# LNA_DIV.net
KiCad netlist of a schematic drawn in Altium Designer
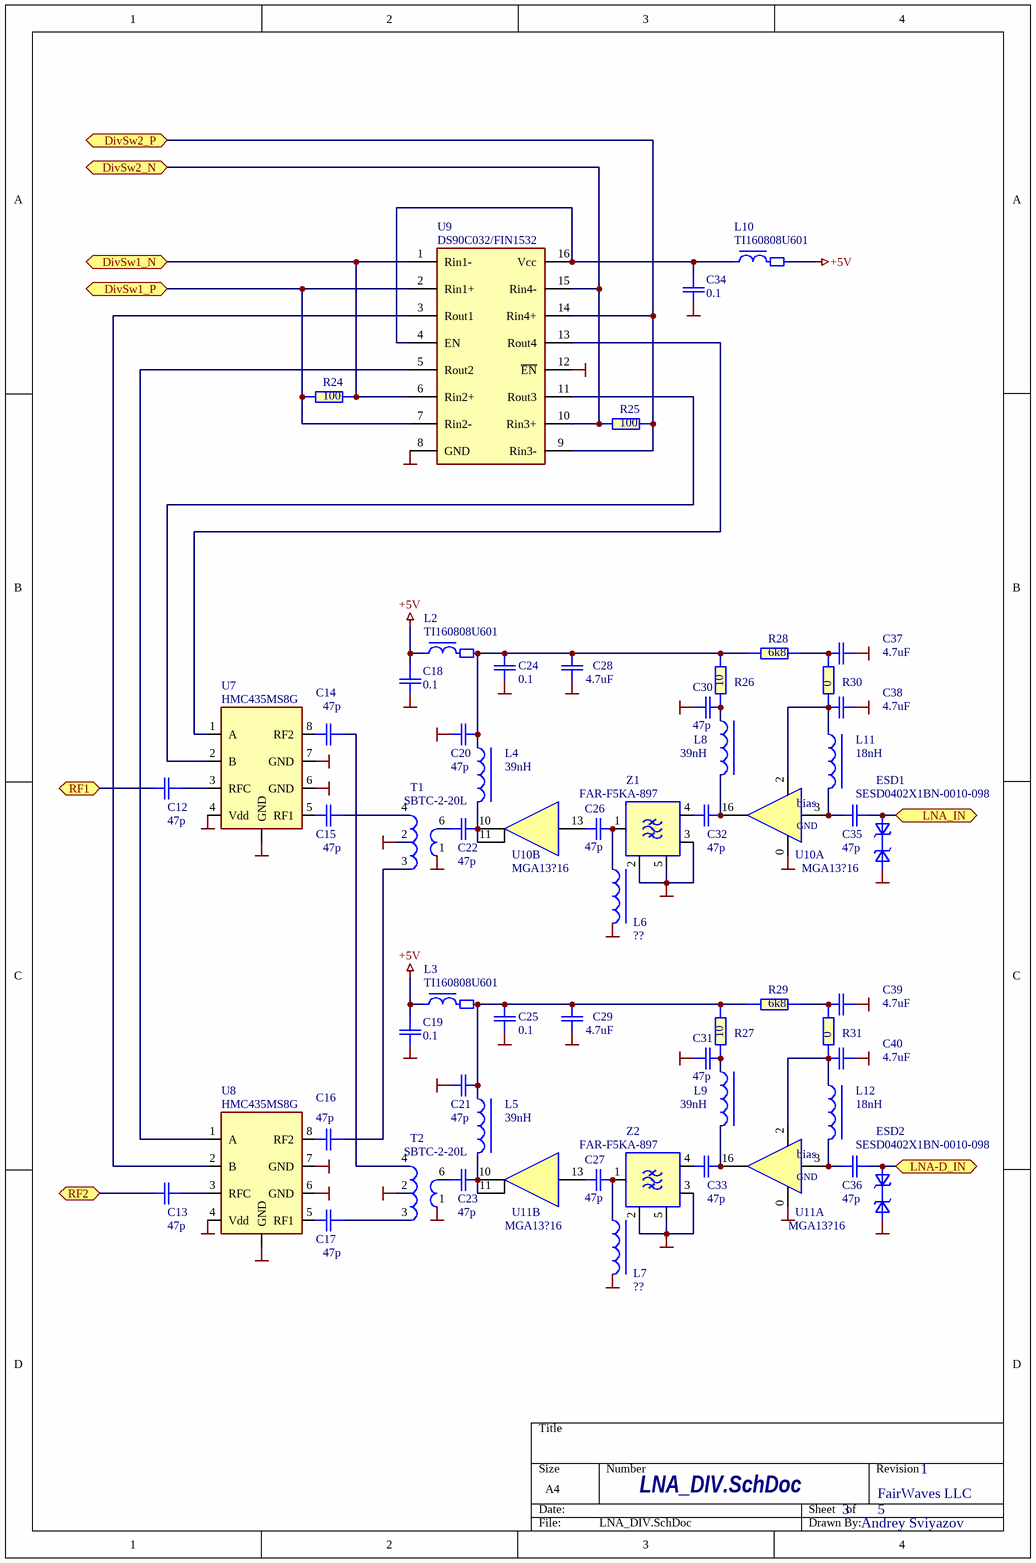
[diagram p0: LNA_DIV.SchDoc]

(export (version "E")
  (design (tool "Eeschema 10.0.6"))
  (components
    (comp (ref "C12")
      (value "47p")
      (footprint "C0603-PHILLIPS")
      (description "Capacitor")
      (fields (field (name "MANUFACTURER") "MURATA") (field (name "TOLERANCE") "20%"))
      (libsource (lib "altium-import") (part "root_1_C0603_"))
    )
    (comp (ref "C13")
      (value "47p")
      (footprint "C0603-PHILLIPS")
      (description "Capacitor")
      (fields (field (name "MANUFACTURER") "MURATA") (field (name "TOLERANCE") "20%"))
      (libsource (lib "altium-import") (part "root_1_C0603_"))
    )
    (comp (ref "C14")
      (value "47p")
      (footprint "C0603-PHILLIPS")
      (description "Capacitor")
      (fields (field (name "MANUFACTURER") "MURATA") (field (name "TOLERANCE") "20%"))
      (libsource (lib "altium-import") (part "root_1_C0603_"))
    )
    (comp (ref "C15")
      (value "47p")
      (footprint "C0603-PHILLIPS")
      (description "Capacitor")
      (fields (field (name "MANUFACTURER") "MURATA") (field (name "TOLERANCE") "20%"))
      (libsource (lib "altium-import") (part "root_1_C0603_"))
    )
    (comp (ref "C16")
      (value "47p")
      (footprint "C0603-PHILLIPS")
      (description "Capacitor")
      (fields (field (name "MANUFACTURER") "MURATA") (field (name "TOLERANCE") "20%"))
      (libsource (lib "altium-import") (part "root_1_C0603_"))
    )
    (comp (ref "C17")
      (value "47p")
      (footprint "C0603-PHILLIPS")
      (description "Capacitor")
      (fields (field (name "MANUFACTURER") "MURATA") (field (name "TOLERANCE") "20%"))
      (libsource (lib "altium-import") (part "root_1_C0603_"))
    )
    (comp (ref "C18")
      (value "0.1")
      (footprint "C0603-Phillips")
      (description "Capacitor")
      (fields (field (name "MANUFACTURER") "MURATA") (field (name "TOLERANCE") "20%"))
      (libsource (lib "Capacitors") (part "C0603"))
    )
    (comp (ref "C19")
      (value "0.1")
      (footprint "C0603-Phillips")
      (description "Capacitor")
      (fields (field (name "MANUFACTURER") "MURATA") (field (name "TOLERANCE") "20%"))
      (libsource (lib "Capacitors") (part "C0603"))
    )
    (comp (ref "C20")
      (value "47p")
      (footprint "C0603-PHILLIPS")
      (description "Capacitor")
      (fields (field (name "MANUFACTURER") "MURATA") (field (name "TOLERANCE") "20%"))
      (libsource (lib "altium-import") (part "root_1_C0603_"))
    )
    (comp (ref "C21")
      (value "47p")
      (footprint "C0603-PHILLIPS")
      (description "Capacitor")
      (fields (field (name "MANUFACTURER") "MURATA") (field (name "TOLERANCE") "20%"))
      (libsource (lib "altium-import") (part "root_1_C0603_"))
    )
    (comp (ref "C22")
      (value "47p")
      (footprint "C0603-PHILLIPS")
      (description "Capacitor")
      (fields (field (name "MANUFACTURER") "MURATA") (field (name "TOLERANCE") "20%"))
      (libsource (lib "altium-import") (part "root_1_C0603_"))
    )
    (comp (ref "C23")
      (value "47p")
      (footprint "C0603-PHILLIPS")
      (description "Capacitor")
      (fields (field (name "MANUFACTURER") "MURATA") (field (name "TOLERANCE") "20%"))
      (libsource (lib "altium-import") (part "root_1_C0603_"))
    )
    (comp (ref "C24")
      (value "0.1")
      (footprint "C0603-Phillips")
      (description "Capacitor")
      (fields (field (name "MANUFACTURER") "MURATA") (field (name "TOLERANCE") "20%"))
      (libsource (lib "Capacitors") (part "C0603"))
    )
    (comp (ref "C25")
      (value "0.1")
      (footprint "C0603-Phillips")
      (description "Capacitor")
      (fields (field (name "MANUFACTURER") "MURATA") (field (name "TOLERANCE") "20%"))
      (libsource (lib "Capacitors") (part "C0603"))
    )
    (comp (ref "C26")
      (value "47p")
      (footprint "C0603-PHILLIPS")
      (description "Capacitor")
      (fields (field (name "MANUFACTURER") "MURATA") (field (name "TOLERANCE") "20%"))
      (libsource (lib "altium-import") (part "root_1_C0603_"))
    )
    (comp (ref "C27")
      (value "47p")
      (footprint "C0603-PHILLIPS")
      (description "Capacitor")
      (fields (field (name "MANUFACTURER") "MURATA") (field (name "TOLERANCE") "20%"))
      (libsource (lib "altium-import") (part "root_1_C0603_"))
    )
    (comp (ref "C28")
      (value "4.7uF")
      (footprint "C0603-Phillips")
      (description "Capacitor")
      (fields (field (name "MANUFACTURER") "MURATA") (field (name "TOLERANCE") "20%"))
      (libsource (lib "Capacitors") (part "C0603"))
    )
    (comp (ref "C29")
      (value "4.7uF")
      (footprint "C0603-Phillips")
      (description "Capacitor")
      (fields (field (name "MANUFACTURER") "MURATA") (field (name "TOLERANCE") "20%"))
      (libsource (lib "Capacitors") (part "C0603"))
    )
    (comp (ref "C30")
      (value "47p")
      (footprint "C0603-PHILLIPS")
      (description "Capacitor")
      (fields (field (name "MANUFACTURER") "MURATA") (field (name "TOLERANCE") "20%"))
      (libsource (lib "altium-import") (part "root_3_C0603_"))
    )
    (comp (ref "C31")
      (value "47p")
      (footprint "C0603-PHILLIPS")
      (description "Capacitor")
      (fields (field (name "MANUFACTURER") "MURATA") (field (name "TOLERANCE") "20%"))
      (libsource (lib "altium-import") (part "root_3_C0603_"))
    )
    (comp (ref "C32")
      (value "47p")
      (footprint "C0603-PHILLIPS")
      (description "Capacitor")
      (fields (field (name "MANUFACTURER") "MURATA") (field (name "TOLERANCE") "20%"))
      (libsource (lib "altium-import") (part "root_1_C0603_"))
    )
    (comp (ref "C33")
      (value "47p")
      (footprint "C0603-PHILLIPS")
      (description "Capacitor")
      (fields (field (name "MANUFACTURER") "MURATA") (field (name "TOLERANCE") "20%"))
      (libsource (lib "altium-import") (part "root_1_C0603_"))
    )
    (comp (ref "C34")
      (value "0.1")
      (footprint "C0603-Phillips")
      (description "Capacitor")
      (fields (field (name "MANUFACTURER") "MURATA") (field (name "TOLERANCE") "20%"))
      (libsource (lib "Capacitors") (part "C0603"))
    )
    (comp (ref "C35")
      (value "47p")
      (footprint "C0603-PHILLIPS")
      (description "Capacitor")
      (fields (field (name "MANUFACTURER") "MURATA") (field (name "TOLERANCE") "20%"))
      (libsource (lib "altium-import") (part "root_1_C0603_"))
    )
    (comp (ref "C36")
      (value "47p")
      (footprint "C0603-PHILLIPS")
      (description "Capacitor")
      (fields (field (name "MANUFACTURER") "MURATA") (field (name "TOLERANCE") "20%"))
      (libsource (lib "altium-import") (part "root_1_C0603_"))
    )
    (comp (ref "C37")
      (value "4.7uF")
      (footprint "C0603-Phillips")
      (description "Capacitor")
      (fields (field (name "MANUFACTURER") "MURATA") (field (name "TOLERANCE") "20%"))
      (libsource (lib "Capacitors") (part "C0603"))
    )
    (comp (ref "C38")
      (value "4.7uF")
      (footprint "C0603-Phillips")
      (description "Capacitor")
      (fields (field (name "MANUFACTURER") "MURATA") (field (name "TOLERANCE") "20%"))
      (libsource (lib "Capacitors") (part "C0603"))
    )
    (comp (ref "C39")
      (value "4.7uF")
      (footprint "C0603-Phillips")
      (description "Capacitor")
      (fields (field (name "MANUFACTURER") "MURATA") (field (name "TOLERANCE") "20%"))
      (libsource (lib "Capacitors") (part "C0603"))
    )
    (comp (ref "C40")
      (value "4.7uF")
      (footprint "C0603-Phillips")
      (description "Capacitor")
      (fields (field (name "MANUFACTURER") "MURATA") (field (name "TOLERANCE") "20%"))
      (libsource (lib "Capacitors") (part "C0603"))
    )
    (comp (ref "ESD1")
      (value "SESD0402X1BN-0010-098")
      (footprint "R0402-Phillips")
      (description "ESD diod bi-directional")
      (fields (field (name "MANUFACTURER") "Tyco Electronics Corp"))
      (libsource (lib "*") (part "SESD0402X"))
    )
    (comp (ref "ESD2")
      (value "SESD0402X1BN-0010-098")
      (footprint "R0402-Phillips")
      (description "ESD diod bi-directional")
      (fields (field (name "MANUFACTURER") "Tyco Electronics Corp"))
      (libsource (lib "*") (part "SESD0402X"))
    )
    (comp (ref "L2")
      (value "TI160808U601")
      (footprint "Andy:Ti160808-Phillips")
      (description "Choke")
      (fields (field (name "MANUFACTURER") "MURATA"))
      (libsource (lib "altium-import") (part "root_0_TI160808_"))
    )
    (comp (ref "L3")
      (value "TI160808U601")
      (footprint "Andy:Ti160808-Phillips")
      (description "Choke")
      (fields (field (name "MANUFACTURER") "MURATA"))
      (libsource (lib "altium-import") (part "root_0_TI160808_"))
    )
    (comp (ref "L4")
      (value "39nH")
      (footprint "Andy:TF160808-Phillips")
      (description "Coil")
      (fields (field (name "MANUFACTURER") "SMD"))
      (libsource (lib "altium-import") (part "root_3_TF160808_"))
    )
    (comp (ref "L5")
      (value "39nH")
      (footprint "Andy:TF160808-Phillips")
      (description "Coil")
      (fields (field (name "MANUFACTURER") "SMD"))
      (libsource (lib "altium-import") (part "root_3_TF160808_"))
    )
    (comp (ref "L6")
      (value "??")
      (footprint "TF160808-Phillips")
      (description "Coil")
      (fields (field (name "MANUFACTURER") "SMD"))
      (libsource (lib "Inductance Transformers") (part "TF160808"))
    )
    (comp (ref "L7")
      (value "??")
      (footprint "TF160808-Phillips")
      (description "Coil")
      (fields (field (name "MANUFACTURER") "SMD"))
      (libsource (lib "Inductance Transformers") (part "TF160808"))
    )
    (comp (ref "L8")
      (value "39nH")
      (footprint "Andy:TF160808-Phillips")
      (description "Coil")
      (fields (field (name "MANUFACTURER") "SMD"))
      (libsource (lib "altium-import") (part "root_3_TF160808_"))
    )
    (comp (ref "L9")
      (value "39nH")
      (footprint "Andy:TF160808-Phillips")
      (description "Coil")
      (fields (field (name "MANUFACTURER") "SMD"))
      (libsource (lib "altium-import") (part "root_3_TF160808_"))
    )
    (comp (ref "L10")
      (value "TI160808U601")
      (footprint "Andy:Ti160808-Phillips")
      (description "Choke")
      (fields (field (name "MANUFACTURER") "MURATA"))
      (libsource (lib "altium-import") (part "root_0_TI160808_"))
    )
    (comp (ref "L11")
      (value "18nH")
      (footprint "Andy:TF160808-Phillips")
      (description "Coil")
      (fields (field (name "MANUFACTURER") "SMD"))
      (libsource (lib "altium-import") (part "root_3_TF160808_"))
    )
    (comp (ref "L12")
      (value "18nH")
      (footprint "Andy:TF160808-Phillips")
      (description "Coil")
      (fields (field (name "MANUFACTURER") "SMD"))
      (libsource (lib "altium-import") (part "root_3_TF160808_"))
    )
    (comp (ref "R24")
      (value "100")
      (footprint "R0603-PHILLIPS")
      (description "Resistor")
      (fields (field (name "MANUFACTURER") "YAGEO") (field (name "TOLERANCE") "5%"))
      (libsource (lib "altium-import") (part "root_1_R0603_"))
    )
    (comp (ref "R25")
      (value "100")
      (footprint "R0603-PHILLIPS")
      (description "Resistor")
      (fields (field (name "MANUFACTURER") "YAGEO") (field (name "TOLERANCE") "5%"))
      (libsource (lib "altium-import") (part "root_1_R0603_"))
    )
    (comp (ref "R26")
      (value "10")
      (footprint "R0603-PHILLIPS")
      (description "Resistor")
      (fields (field (name "MANUFACTURER") "YAGEO") (field (name "TOLERANCE") "5%"))
      (libsource (lib "altium-import") (part "root_2_R0603_"))
    )
    (comp (ref "R27")
      (value "10")
      (footprint "R0603-PHILLIPS")
      (description "Resistor")
      (fields (field (name "MANUFACTURER") "YAGEO") (field (name "TOLERANCE") "5%"))
      (libsource (lib "altium-import") (part "root_2_R0603_"))
    )
    (comp (ref "R28")
      (value "6k8")
      (footprint "R0603-PHILLIPS")
      (description "Resistor")
      (fields (field (name "MANUFACTURER") "YAGEO") (field (name "TOLERANCE") "5%"))
      (libsource (lib "altium-import") (part "root_1_R0603_"))
    )
    (comp (ref "R29")
      (value "6k8")
      (footprint "R0603-PHILLIPS")
      (description "Resistor")
      (fields (field (name "MANUFACTURER") "YAGEO") (field (name "TOLERANCE") "5%"))
      (libsource (lib "altium-import") (part "root_1_R0603_"))
    )
    (comp (ref "R30")
      (value "0")
      (footprint "R0603-PHILLIPS")
      (description "Resistor")
      (fields (field (name "MANUFACTURER") "YAGEO") (field (name "TOLERANCE") "5%"))
      (libsource (lib "altium-import") (part "root_2_R0603_"))
    )
    (comp (ref "R31")
      (value "0")
      (footprint "R0603-PHILLIPS")
      (description "Resistor")
      (fields (field (name "MANUFACTURER") "YAGEO") (field (name "TOLERANCE") "5%"))
      (libsource (lib "altium-import") (part "root_2_R0603_"))
    )
    (comp (ref "T1")
      (value "SBTC-2-20L")
      (footprint "AT1030")
      (description "Transformer")
      (fields (field (name "MANUFACTURER") "Mini-Cirquits"))
      (libsource (lib "altium-import") (part "root_0_mirrored_SBTC-2-10L_"))
    )
    (comp (ref "T2")
      (value "SBTC-2-20L")
      (footprint "AT1030")
      (description "Transformer")
      (fields (field (name "MANUFACTURER") "Mini-Cirquits"))
      (libsource (lib "altium-import") (part "root_0_mirrored_SBTC-2-10L_"))
    )
    (comp (ref "U7")
      (value "HMC435MS8G")
      (footprint "MS8G")
      (description "IC")
      (fields (field (name "MANUFACTURER") "Hittite"))
      (libsource (lib "Andy") (part "HMC435MS8G"))
    )
    (comp (ref "U8")
      (value "HMC435MS8G")
      (footprint "MS8G")
      (description "IC")
      (fields (field (name "MANUFACTURER") "Hittite"))
      (libsource (lib "Andy") (part "HMC435MS8G"))
    )
    (comp (ref "U9")
      (value "DS90C032/FIN1532")
      (footprint "SOIC16")
      (description "IC")
      (fields (field (name "MANUFACTURER") "National/Fairchild"))
      (libsource (lib "Andy") (part "DS90C032"))
    )
    (comp (ref "U10")
      (value "MGA13?16")
      (footprint "MGA13x16(GND NC Legs)")
      (description "IC")
      (fields (field (name "MANUFACTURER") "AVAGO"))
      (libsource (lib "Andy") (part "MGA13116"))
    )
    (comp (ref "U11")
      (value "MGA13?16")
      (footprint "MGA13x16(GND NC Legs)")
      (description "IC")
      (fields (field (name "MANUFACTURER") "AVAGO"))
      (libsource (lib "Andy") (part "MGA13116"))
    )
    (comp (ref "Z1")
      (value "FAR-F5KA-897")
      (footprint "SAW-1.4x1x0.5mm")
      (description "SAW Filter")
      (fields (field (name "MANUFACTURER") "Taiyo Yuden"))
      (libsource (lib "Andy") (part "SAW 1.4x1.0-5 SMD"))
    )
    (comp (ref "Z2")
      (value "FAR-F5KA-897")
      (footprint "SAW-1.4x1x0.5mm")
      (description "SAW Filter")
      (fields (field (name "MANUFACTURER") "Taiyo Yuden"))
      (libsource (lib "Andy") (part "SAW 1.4x1.0-5 SMD"))
    )
  )
  (nets
    (net (code "1") (name "+5V") (class "Default")
      (node (ref "C18") (pin "2") (pinfunction "2_2") (pintype "passive"))
      (node (ref "C19") (pin "2") (pinfunction "2_2") (pintype "passive"))
      (node (ref "L10") (pin "2") (pinfunction "2_2") (pintype "passive"))
      (node (ref "L2") (pin "1") (pinfunction "1_1") (pintype "passive"))
      (node (ref "L3") (pin "1") (pinfunction "1_1") (pintype "passive"))
    )
    (net (code "2") (name "/DivSw1_N") (class "Default")
      (node (ref "R24") (pin "2") (pinfunction "2_2") (pintype "passive"))
      (node (ref "U9") (pin "1") (pinfunction "Rin1-_1") (pintype "passive"))
      (node (ref "U9") (pin "6") (pinfunction "Rin2+_6") (pintype "power_in"))
    )
    (net (code "3") (name "/DivSw1_P") (class "Default")
      (node (ref "R24") (pin "1") (pinfunction "1_1") (pintype "passive"))
      (node (ref "U9") (pin "2") (pinfunction "Rin1+_2") (pintype "passive"))
      (node (ref "U9") (pin "7") (pinfunction "Rin2-_7") (pintype "passive"))
    )
    (net (code "4") (name "/DivSw2_N") (class "Default")
      (node (ref "R25") (pin "1") (pinfunction "1_1") (pintype "passive"))
      (node (ref "U9") (pin "10") (pinfunction "Rin3+_10") (pintype "passive"))
      (node (ref "U9") (pin "15") (pinfunction "Rin4-_15") (pintype "passive"))
    )
    (net (code "5") (name "/DivSw2_P") (class "Default")
      (node (ref "R25") (pin "2") (pinfunction "2_2") (pintype "passive"))
      (node (ref "U9") (pin "14") (pinfunction "Rin4+_14") (pintype "power_in"))
      (node (ref "U9") (pin "9") (pinfunction "Rin3-_9") (pintype "passive"))
    )
    (net (code "6") (name "/LNA-D_IN") (class "Default")
      (node (ref "C36") (pin "2") (pinfunction "2_2") (pintype "passive"))
      (node (ref "ESD2") (pin "2") (pinfunction "A2_2") (pintype "passive"))
    )
    (net (code "7") (name "/LNA_IN") (class "Default")
      (node (ref "C35") (pin "2") (pinfunction "2_2") (pintype "passive"))
      (node (ref "ESD1") (pin "2") (pinfunction "A2_2") (pintype "passive"))
    )
    (net (code "8") (name "/RF1") (class "Default")
      (node (ref "C12") (pin "1") (pinfunction "1_1") (pintype "passive"))
    )
    (net (code "9") (name "/RF2") (class "Default")
      (node (ref "C13") (pin "1") (pinfunction "1_1") (pintype "passive"))
    )
    (net (code "10") (name "GND") (class "Default")
      (node (ref "C18") (pin "1") (pinfunction "1_1") (pintype "passive"))
      (node (ref "C19") (pin "1") (pinfunction "1_1") (pintype "passive"))
      (node (ref "C20") (pin "1") (pinfunction "1_1") (pintype "passive"))
      (node (ref "C21") (pin "1") (pinfunction "1_1") (pintype "passive"))
      (node (ref "C24") (pin "1") (pinfunction "1_1") (pintype "passive"))
      (node (ref "C25") (pin "1") (pinfunction "1_1") (pintype "passive"))
      (node (ref "C28") (pin "1") (pinfunction "1_1") (pintype "passive"))
      (node (ref "C29") (pin "1") (pinfunction "1_1") (pintype "passive"))
      (node (ref "C30") (pin "2") (pinfunction "2_2") (pintype "passive"))
      (node (ref "C31") (pin "2") (pinfunction "2_2") (pintype "passive"))
      (node (ref "C34") (pin "1") (pinfunction "1_1") (pintype "passive"))
      (node (ref "C37") (pin "2") (pinfunction "2_2") (pintype "passive"))
      (node (ref "C38") (pin "2") (pinfunction "2_2") (pintype "passive"))
      (node (ref "C39") (pin "2") (pinfunction "2_2") (pintype "passive"))
      (node (ref "C40") (pin "2") (pinfunction "2_2") (pintype "passive"))
      (node (ref "ESD1") (pin "1") (pinfunction "A1_1") (pintype "passive"))
      (node (ref "ESD2") (pin "1") (pinfunction "A1_1") (pintype "passive"))
      (node (ref "L6") (pin "2") (pinfunction "2_2") (pintype "passive"))
      (node (ref "L7") (pin "2") (pinfunction "2_2") (pintype "passive"))
      (node (ref "T1") (pin "1") (pinfunction "1_1") (pintype "passive"))
      (node (ref "T1") (pin "2") (pinfunction "2_2") (pintype "passive"))
      (node (ref "T2") (pin "1") (pinfunction "1_1") (pintype "passive"))
      (node (ref "T2") (pin "2") (pinfunction "2_2") (pintype "passive"))
      (node (ref "U10") (pin "0") (pinfunction "GND_0") (pintype "power_in"))
      (node (ref "U11") (pin "0") (pinfunction "GND_0") (pintype "power_in"))
      (node (ref "U7") (pin "0") (pinfunction "GND_0") (pintype "power_in"))
      (node (ref "U7") (pin "4") (pinfunction "Vdd_4") (pintype "power_in"))
      (node (ref "U7") (pin "6") (pinfunction "GND_6") (pintype "power_in"))
      (node (ref "U7") (pin "7") (pinfunction "GND_7") (pintype "power_in"))
      (node (ref "U8") (pin "0") (pinfunction "GND_0") (pintype "power_in"))
      (node (ref "U8") (pin "4") (pinfunction "Vdd_4") (pintype "power_in"))
      (node (ref "U8") (pin "6") (pinfunction "GND_6") (pintype "power_in"))
      (node (ref "U8") (pin "7") (pinfunction "GND_7") (pintype "power_in"))
      (node (ref "U9") (pin "12") (pinfunction "~{EN}_12") (pintype "passive"))
      (node (ref "U9") (pin "8") (pinfunction "GND_8") (pintype "passive"))
      (node (ref "Z1") (pin "2") (pinfunction "GND_2") (pintype "power_in"))
      (node (ref "Z1") (pin "3") (pinfunction "~{Out}_3") (pintype "passive"))
      (node (ref "Z1") (pin "5") (pinfunction "GND_5") (pintype "power_in"))
      (node (ref "Z2") (pin "2") (pinfunction "GND_2") (pintype "power_in"))
      (node (ref "Z2") (pin "3") (pinfunction "~{Out}_3") (pintype "passive"))
      (node (ref "Z2") (pin "5") (pinfunction "GND_5") (pintype "power_in"))
    )
    (net (code "11") (name "Net-(C14-Pad2)") (class "Default")
      (node (ref "C14") (pin "2") (pinfunction "2_2") (pintype "passive"))
      (node (ref "T2") (pin "4") (pinfunction "4_4") (pintype "passive"))
    )
    (net (code "12") (name "Net-(C15-Pad2)") (class "Default")
      (node (ref "C15") (pin "2") (pinfunction "2_2") (pintype "passive"))
      (node (ref "T1") (pin "4") (pinfunction "4_4") (pintype "passive"))
    )
    (net (code "13") (name "Net-(C16-Pad2)") (class "Default")
      (node (ref "C16") (pin "2") (pinfunction "2_2") (pintype "passive"))
      (node (ref "T1") (pin "3") (pinfunction "3_3") (pintype "passive"))
    )
    (net (code "14") (name "Net-(C17-Pad2)") (class "Default")
      (node (ref "C17") (pin "2") (pinfunction "2_2") (pintype "passive"))
      (node (ref "T2") (pin "3") (pinfunction "3_3") (pintype "passive"))
    )
    (net (code "15") (name "Net-(C20-Pad2)") (class "Default")
      (node (ref "C20") (pin "2") (pinfunction "2_2") (pintype "passive"))
      (node (ref "C24") (pin "2") (pinfunction "2_2") (pintype "passive"))
      (node (ref "C28") (pin "2") (pinfunction "2_2") (pintype "passive"))
      (node (ref "L2") (pin "2") (pinfunction "2_2") (pintype "passive"))
      (node (ref "L4") (pin "1") (pinfunction "1_1") (pintype "passive"))
      (node (ref "R26") (pin "2") (pinfunction "2_2") (pintype "passive"))
      (node (ref "R28") (pin "1") (pinfunction "1_1") (pintype "passive"))
    )
    (net (code "16") (name "Net-(C21-Pad2)") (class "Default")
      (node (ref "C21") (pin "2") (pinfunction "2_2") (pintype "passive"))
      (node (ref "C25") (pin "2") (pinfunction "2_2") (pintype "passive"))
      (node (ref "C29") (pin "2") (pinfunction "2_2") (pintype "passive"))
      (node (ref "L3") (pin "2") (pinfunction "2_2") (pintype "passive"))
      (node (ref "L5") (pin "1") (pinfunction "1_1") (pintype "passive"))
      (node (ref "R27") (pin "2") (pinfunction "2_2") (pintype "passive"))
      (node (ref "R29") (pin "1") (pinfunction "1_1") (pintype "passive"))
    )
    (net (code "17") (name "Net-(C22-Pad1)") (class "Default")
      (node (ref "C22") (pin "1") (pinfunction "1_1") (pintype "passive"))
      (node (ref "T1") (pin "6") (pinfunction "6_6") (pintype "passive"))
    )
    (net (code "18") (name "Net-(C22-Pad2)") (class "Default")
      (node (ref "C22") (pin "2") (pinfunction "2_2") (pintype "passive"))
      (node (ref "L4") (pin "2") (pinfunction "2_2") (pintype "passive"))
      (node (ref "U10") (pin "10") (pinfunction "Out2/VDD_10") (pintype "passive"))
      (node (ref "U10") (pin "11") (pinfunction "Out2/VDD_11") (pintype "passive"))
    )
    (net (code "19") (name "Net-(C23-Pad1)") (class "Default")
      (node (ref "C23") (pin "1") (pinfunction "1_1") (pintype "passive"))
      (node (ref "T2") (pin "6") (pinfunction "6_6") (pintype "passive"))
    )
    (net (code "20") (name "Net-(C23-Pad2)") (class "Default")
      (node (ref "C23") (pin "2") (pinfunction "2_2") (pintype "passive"))
      (node (ref "L5") (pin "2") (pinfunction "2_2") (pintype "passive"))
      (node (ref "U11") (pin "10") (pinfunction "Out2/VDD_10") (pintype "passive"))
      (node (ref "U11") (pin "11") (pinfunction "Out2/VDD_11") (pintype "passive"))
    )
    (net (code "21") (name "Net-(C30-Pad1)") (class "Default")
      (node (ref "C30") (pin "1") (pinfunction "1_1") (pintype "passive"))
      (node (ref "L8") (pin "1") (pinfunction "1_1") (pintype "passive"))
      (node (ref "R26") (pin "1") (pinfunction "1_1") (pintype "passive"))
    )
    (net (code "22") (name "Net-(C31-Pad1)") (class "Default")
      (node (ref "C31") (pin "1") (pinfunction "1_1") (pintype "passive"))
      (node (ref "L9") (pin "1") (pinfunction "1_1") (pintype "passive"))
      (node (ref "R27") (pin "1") (pinfunction "1_1") (pintype "passive"))
    )
    (net (code "23") (name "Net-(C37-Pad1)") (class "Default")
      (node (ref "C37") (pin "1") (pinfunction "1_1") (pintype "passive"))
      (node (ref "R28") (pin "2") (pinfunction "2_2") (pintype "passive"))
      (node (ref "R30") (pin "2") (pinfunction "2_2") (pintype "passive"))
    )
    (net (code "24") (name "Net-(C39-Pad1)") (class "Default")
      (node (ref "C39") (pin "1") (pinfunction "1_1") (pintype "passive"))
      (node (ref "R29") (pin "2") (pinfunction "2_2") (pintype "passive"))
      (node (ref "R31") (pin "2") (pinfunction "2_2") (pintype "passive"))
    )
    (net (code "25") (name "Net-(U7-A)") (class "Default")
      (node (ref "U7") (pin "1") (pinfunction "A_1") (pintype "passive"))
      (node (ref "U9") (pin "13") (pinfunction "Rout4_13") (pintype "passive"))
    )
    (net (code "26") (name "Net-(U7-B)") (class "Default")
      (node (ref "U7") (pin "2") (pinfunction "B_2") (pintype "passive"))
      (node (ref "U9") (pin "11") (pinfunction "Rout3_11") (pintype "passive"))
    )
    (net (code "27") (name "Net-(U7-RF1)") (class "Default")
      (node (ref "C15") (pin "1") (pinfunction "1_1") (pintype "passive"))
      (node (ref "U7") (pin "5") (pinfunction "RF1_5") (pintype "passive"))
    )
    (net (code "28") (name "Net-(U7-RF2)") (class "Default")
      (node (ref "C14") (pin "1") (pinfunction "1_1") (pintype "passive"))
      (node (ref "U7") (pin "8") (pinfunction "RF2_8") (pintype "passive"))
    )
    (net (code "29") (name "Net-(U7-RFC)") (class "Default")
      (node (ref "C12") (pin "2") (pinfunction "2_2") (pintype "passive"))
      (node (ref "U7") (pin "3") (pinfunction "RFC_3") (pintype "power_in"))
    )
    (net (code "30") (name "Net-(U8-A)") (class "Default")
      (node (ref "U8") (pin "1") (pinfunction "A_1") (pintype "passive"))
      (node (ref "U9") (pin "5") (pinfunction "Rout2_5") (pintype "passive"))
    )
    (net (code "31") (name "Net-(U8-B)") (class "Default")
      (node (ref "U8") (pin "2") (pinfunction "B_2") (pintype "passive"))
      (node (ref "U9") (pin "3") (pinfunction "Rout1_3") (pintype "passive"))
    )
    (net (code "32") (name "Net-(U8-RF1)") (class "Default")
      (node (ref "C17") (pin "1") (pinfunction "1_1") (pintype "passive"))
      (node (ref "U8") (pin "5") (pinfunction "RF1_5") (pintype "passive"))
    )
    (net (code "33") (name "Net-(U8-RF2)") (class "Default")
      (node (ref "C16") (pin "1") (pinfunction "1_1") (pintype "passive"))
      (node (ref "U8") (pin "8") (pinfunction "RF2_8") (pintype "passive"))
    )
    (net (code "34") (name "Net-(U8-RFC)") (class "Default")
      (node (ref "C13") (pin "2") (pinfunction "2_2") (pintype "passive"))
      (node (ref "U8") (pin "3") (pinfunction "RFC_3") (pintype "power_in"))
    )
    (net (code "35") (name "Net-(U9-EN)") (class "Default")
      (node (ref "C34") (pin "2") (pinfunction "2_2") (pintype "passive"))
      (node (ref "L10") (pin "1") (pinfunction "1_1") (pintype "passive"))
      (node (ref "U9") (pin "16") (pinfunction "Vcc_16") (pintype "passive"))
      (node (ref "U9") (pin "4") (pinfunction "EN_4") (pintype "passive"))
    )
    (net (code "36") (name "Net-(U10A-BIAS)") (class "Default")
      (node (ref "C38") (pin "1") (pinfunction "1_1") (pintype "passive"))
      (node (ref "L11") (pin "1") (pinfunction "1_1") (pintype "passive"))
      (node (ref "R30") (pin "1") (pinfunction "1_1") (pintype "passive"))
      (node (ref "U10") (pin "2") (pinfunction "BIAS_2") (pintype "passive"))
    )
    (net (code "37") (name "Net-(U10A-In1)") (class "Default")
      (node (ref "C35") (pin "1") (pinfunction "1_1") (pintype "passive"))
      (node (ref "L11") (pin "2") (pinfunction "2_2") (pintype "passive"))
      (node (ref "U10") (pin "3") (pinfunction "In1_3") (pintype "passive"))
    )
    (net (code "38") (name "Net-(U10A-Out1{slash}VDD)") (class "Default")
      (node (ref "C32") (pin "2") (pinfunction "2_2") (pintype "passive"))
      (node (ref "L8") (pin "2") (pinfunction "2_2") (pintype "passive"))
      (node (ref "U10") (pin "16") (pinfunction "Out1/VDD_16") (pintype "passive"))
    )
    (net (code "39") (name "Net-(U10B-In2)") (class "Default")
      (node (ref "C26") (pin "1") (pinfunction "1_1") (pintype "passive"))
      (node (ref "U10") (pin "13") (pinfunction "In2_13") (pintype "passive"))
    )
    (net (code "40") (name "Net-(U11A-BIAS)") (class "Default")
      (node (ref "C40") (pin "1") (pinfunction "1_1") (pintype "passive"))
      (node (ref "L12") (pin "1") (pinfunction "1_1") (pintype "passive"))
      (node (ref "R31") (pin "1") (pinfunction "1_1") (pintype "passive"))
      (node (ref "U11") (pin "2") (pinfunction "BIAS_2") (pintype "passive"))
    )
    (net (code "41") (name "Net-(U11A-In1)") (class "Default")
      (node (ref "C36") (pin "1") (pinfunction "1_1") (pintype "passive"))
      (node (ref "L12") (pin "2") (pinfunction "2_2") (pintype "passive"))
      (node (ref "U11") (pin "3") (pinfunction "In1_3") (pintype "passive"))
    )
    (net (code "42") (name "Net-(U11A-Out1{slash}VDD)") (class "Default")
      (node (ref "C33") (pin "2") (pinfunction "2_2") (pintype "passive"))
      (node (ref "L9") (pin "2") (pinfunction "2_2") (pintype "passive"))
      (node (ref "U11") (pin "16") (pinfunction "Out1/VDD_16") (pintype "passive"))
    )
    (net (code "43") (name "Net-(U11B-In2)") (class "Default")
      (node (ref "C27") (pin "1") (pinfunction "1_1") (pintype "passive"))
      (node (ref "U11") (pin "13") (pinfunction "In2_13") (pintype "passive"))
    )
    (net (code "44") (name "Net-(Z1-IN)") (class "Default")
      (node (ref "C26") (pin "2") (pinfunction "2_2") (pintype "passive"))
      (node (ref "L6") (pin "1") (pinfunction "1_1") (pintype "passive"))
      (node (ref "Z1") (pin "1") (pinfunction "IN_1") (pintype "passive"))
    )
    (net (code "45") (name "Net-(Z1-Out)") (class "Default")
      (node (ref "C32") (pin "1") (pinfunction "1_1") (pintype "passive"))
      (node (ref "Z1") (pin "4") (pinfunction "Out_4") (pintype "passive"))
    )
    (net (code "46") (name "Net-(Z2-IN)") (class "Default")
      (node (ref "C27") (pin "2") (pinfunction "2_2") (pintype "passive"))
      (node (ref "L7") (pin "1") (pinfunction "1_1") (pintype "passive"))
      (node (ref "Z2") (pin "1") (pinfunction "IN_1") (pintype "passive"))
    )
    (net (code "47") (name "Net-(Z2-Out)") (class "Default")
      (node (ref "C33") (pin "1") (pinfunction "1_1") (pintype "passive"))
      (node (ref "Z2") (pin "4") (pinfunction "Out_4") (pintype "passive"))
    )
  )
)
